# PROC051C_SOP_Headers_Reference.net
KiCad netlist of a schematic drawn in Altium Designer
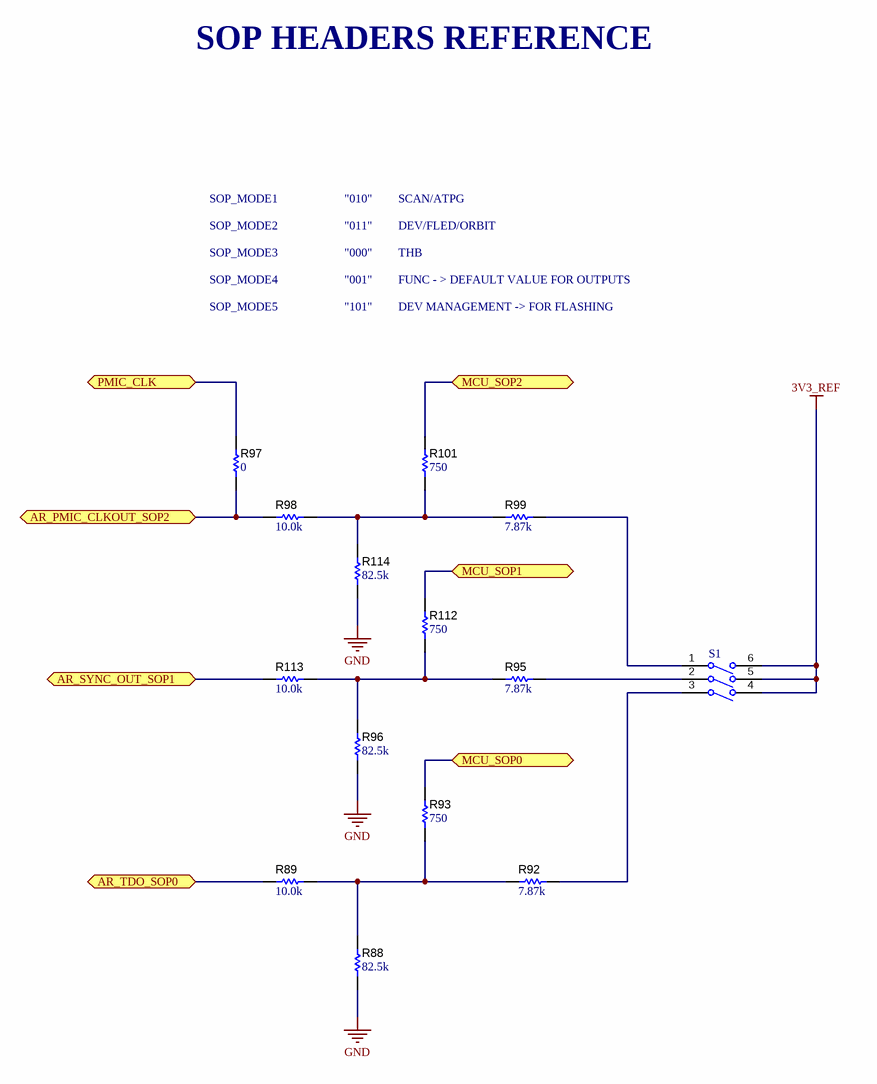
[diagram p0: PROC051C_SOP_Headers_Reference.SchDoc]

(export (version "E")
  (design (tool "Eeschema 10.0.6"))
  (components
    (comp (ref "R88")
      (value "CRCW040282K5FKED")
      (footprint "0402L")
      (description "RES, 82.5 k, 1%, 0.063 W, AEC-Q200 Grade 0, 0402")
      (fields (field (name "MANUFACTURER") "Vishay-Dale") (field (name "VALUEDISPLAYED") "82.5k"))
      (libsource (lib "Altium Vault - TI") (part "Resistor"))
    )
    (comp (ref "R89")
      (value "CRCW040210K0FKED")
      (footprint "0402L")
      (description "RES, 10.0 k, 1%, 0.063 W, AEC-Q200 Grade 0, 0402")
      (fields (field (name "MANUFACTURER") "Vishay-Dale") (field (name "VALUEDISPLAYED") "10.0k"))
      (libsource (lib "Altium Vault - TI") (part "Resistor"))
    )
    (comp (ref "R92")
      (value "CRCW04027K87FKED")
      (footprint "0402L")
      (description "RES, 7.87 k, 1%, 0.063 W, AEC-Q200 Grade 0, 0402")
      (fields (field (name "MANUFACTURER") "Vishay-Dale") (field (name "VALUEDISPLAYED") "7.87k"))
      (libsource (lib "Altium Vault - TI") (part "Resistor"))
    )
    (comp (ref "R93")
      (value "CRCW0402750RFKED")
      (footprint "0402L")
      (description "RES, 750, 1%, 0.063 W, AEC-Q200 Grade 0, 0402")
      (fields (field (name "MANUFACTURER") "Vishay-Dale") (field (name "VALUEDISPLAYED") "750"))
      (libsource (lib "Altium Vault - TI") (part "Resistor"))
    )
    (comp (ref "R95")
      (value "CRCW04027K87FKED")
      (footprint "0402L")
      (description "RES, 7.87 k, 1%, 0.063 W, AEC-Q200 Grade 0, 0402")
      (fields (field (name "MANUFACTURER") "Vishay-Dale") (field (name "VALUEDISPLAYED") "7.87k"))
      (libsource (lib "Altium Vault - TI") (part "Resistor"))
    )
    (comp (ref "R96")
      (value "CRCW040282K5FKED")
      (footprint "0402L")
      (description "RES, 82.5 k, 1%, 0.063 W, AEC-Q200 Grade 0, 0402")
      (fields (field (name "MANUFACTURER") "Vishay-Dale") (field (name "VALUEDISPLAYED") "82.5k"))
      (libsource (lib "Altium Vault - TI") (part "Resistor"))
    )
    (comp (ref "R97")
      (value "ERJ-2GE0R00X")
      (footprint "0402L")
      (description "RES, 0, 5%, 0.1 W, AEC-Q200 Grade 0, 0402")
      (fields (field (name "MANUFACTURER") "Panasonic") (field (name "VALUEDISPLAYED") "0"))
      (libsource (lib "Altium Vault - TI") (part "Resistor"))
    )
    (comp (ref "R98")
      (value "CRCW040210K0FKED")
      (footprint "0402L")
      (description "RES, 10.0 k, 1%, 0.063 W, AEC-Q200 Grade 0, 0402")
      (fields (field (name "MANUFACTURER") "Vishay-Dale") (field (name "VALUEDISPLAYED") "10.0k"))
      (libsource (lib "Altium Vault - TI") (part "Resistor"))
    )
    (comp (ref "R99")
      (value "CRCW04027K87FKED")
      (footprint "0402L")
      (description "RES, 7.87 k, 1%, 0.063 W, AEC-Q200 Grade 0, 0402")
      (fields (field (name "MANUFACTURER") "Vishay-Dale") (field (name "VALUEDISPLAYED") "7.87k"))
      (libsource (lib "Altium Vault - TI") (part "Resistor"))
    )
    (comp (ref "R101")
      (value "CRCW0402750RFKED")
      (footprint "0402L")
      (description "RES, 750, 1%, 0.063 W, AEC-Q200 Grade 0, 0402")
      (fields (field (name "MANUFACTURER") "Vishay-Dale") (field (name "VALUEDISPLAYED") "750"))
      (libsource (lib "Altium Vault - TI") (part "Resistor"))
    )
    (comp (ref "R112")
      (value "CRCW0402750RFKED")
      (footprint "0402L")
      (description "RES, 750, 1%, 0.063 W, AEC-Q200 Grade 0, 0402")
      (fields (field (name "MANUFACTURER") "Vishay-Dale") (field (name "VALUEDISPLAYED") "750"))
      (libsource (lib "Altium Vault - TI") (part "Resistor"))
    )
    (comp (ref "R113")
      (value "CRCW040210K0FKED")
      (footprint "0402L")
      (description "RES, 10.0 k, 1%, 0.063 W, AEC-Q200 Grade 0, 0402")
      (fields (field (name "MANUFACTURER") "Vishay-Dale") (field (name "VALUEDISPLAYED") "10.0k"))
      (libsource (lib "Altium Vault - TI") (part "Resistor"))
    )
    (comp (ref "R114")
      (value "CRCW040282K5FKED")
      (footprint "0402L")
      (description "RES, 82.5 k, 1%, 0.063 W, AEC-Q200 Grade 0, 0402")
      (fields (field (name "MANUFACTURER") "Vishay-Dale") (field (name "VALUEDISPLAYED") "82.5k"))
      (libsource (lib "Altium Vault - TI") (part "Resistor"))
    )
    (comp (ref "S1")
      (value "219-3MST")
      (footprint "SW_219-3MST")
      (description "Switch, SPST, Slide, Off-On, 3 Pos, 0.1A, 20V, SMD")
      (fields
        (field (name "MANUFACTURER") "CTS Electrocomponents")
        (field (name "PUBLISHER") "Texas Instruments")
      )
      (libsource (lib "Altium Vault - TI") (part "CMP-0002269-1"))
    )
  )
  (nets
    (net (code "1") (name "/AR_PMIC_CLKOUT_SOP2") (class "Default")
      (node (ref "R97") (pin "1") (pinfunction "1_1") (pintype "passive"))
      (node (ref "R98") (pin "1") (pinfunction "1_1") (pintype "passive"))
    )
    (net (code "2") (name "/AR_SYNC_OUT_SOP1") (class "Default")
      (node (ref "R113") (pin "1") (pinfunction "1_1") (pintype "passive"))
    )
    (net (code "3") (name "/AR_TDO_SOP0") (class "Default")
      (node (ref "R89") (pin "1") (pinfunction "1_1") (pintype "passive"))
    )
    (net (code "4") (name "/MCU_SOP0") (class "Default")
      (node (ref "R93") (pin "2") (pinfunction "2_2") (pintype "passive"))
    )
    (net (code "5") (name "/MCU_SOP1") (class "Default")
      (node (ref "R112") (pin "2") (pinfunction "2_2") (pintype "passive"))
    )
    (net (code "6") (name "/MCU_SOP2") (class "Default")
      (node (ref "R101") (pin "2") (pinfunction "2_2") (pintype "passive"))
    )
    (net (code "7") (name "/PMIC_CLK") (class "Default")
      (node (ref "R97") (pin "2") (pinfunction "2_2") (pintype "passive"))
    )
    (net (code "8") (name "3V3_REF") (class "Default")
      (node (ref "S1") (pin "4") (pinfunction "B3_4") (pintype "passive"))
      (node (ref "S1") (pin "5") (pinfunction "B2_5") (pintype "passive"))
      (node (ref "S1") (pin "6") (pinfunction "B1_6") (pintype "passive"))
    )
    (net (code "9") (name "GND") (class "Default")
      (node (ref "R114") (pin "1") (pinfunction "1_1") (pintype "passive"))
      (node (ref "R88") (pin "1") (pinfunction "1_1") (pintype "passive"))
      (node (ref "R96") (pin "1") (pinfunction "1_1") (pintype "passive"))
    )
    (net (code "10") (name "Net-(R88-Pad2)") (class "Default")
      (node (ref "R88") (pin "2") (pinfunction "2_2") (pintype "passive"))
      (node (ref "R89") (pin "2") (pinfunction "2_2") (pintype "passive"))
      (node (ref "R92") (pin "1") (pinfunction "1_1") (pintype "passive"))
      (node (ref "R93") (pin "1") (pinfunction "1_1") (pintype "passive"))
    )
    (net (code "11") (name "Net-(R101-Pad1)") (class "Default")
      (node (ref "R101") (pin "1") (pinfunction "1_1") (pintype "passive"))
      (node (ref "R114") (pin "2") (pinfunction "2_2") (pintype "passive"))
      (node (ref "R98") (pin "2") (pinfunction "2_2") (pintype "passive"))
      (node (ref "R99") (pin "1") (pinfunction "1_1") (pintype "passive"))
    )
    (net (code "12") (name "Net-(R112-Pad1)") (class "Default")
      (node (ref "R112") (pin "1") (pinfunction "1_1") (pintype "passive"))
      (node (ref "R113") (pin "2") (pinfunction "2_2") (pintype "passive"))
      (node (ref "R95") (pin "1") (pinfunction "1_1") (pintype "passive"))
      (node (ref "R96") (pin "2") (pinfunction "2_2") (pintype "passive"))
    )
    (net (code "13") (name "Net-(S1-A1)") (class "Default")
      (node (ref "R99") (pin "2") (pinfunction "2_2") (pintype "passive"))
      (node (ref "S1") (pin "1") (pinfunction "A1_1") (pintype "passive"))
    )
    (net (code "14") (name "Net-(S1-A2)") (class "Default")
      (node (ref "R95") (pin "2") (pinfunction "2_2") (pintype "passive"))
      (node (ref "S1") (pin "2") (pinfunction "A2_2") (pintype "passive"))
    )
    (net (code "15") (name "Net-(S1-A3)") (class "Default")
      (node (ref "R92") (pin "2") (pinfunction "2_2") (pintype "passive"))
      (node (ref "S1") (pin "3") (pinfunction "A3_3") (pintype "passive"))
    )
  )
)
